# Reader_3_0.net
KiCad netlist of a schematic drawn in EAGLE
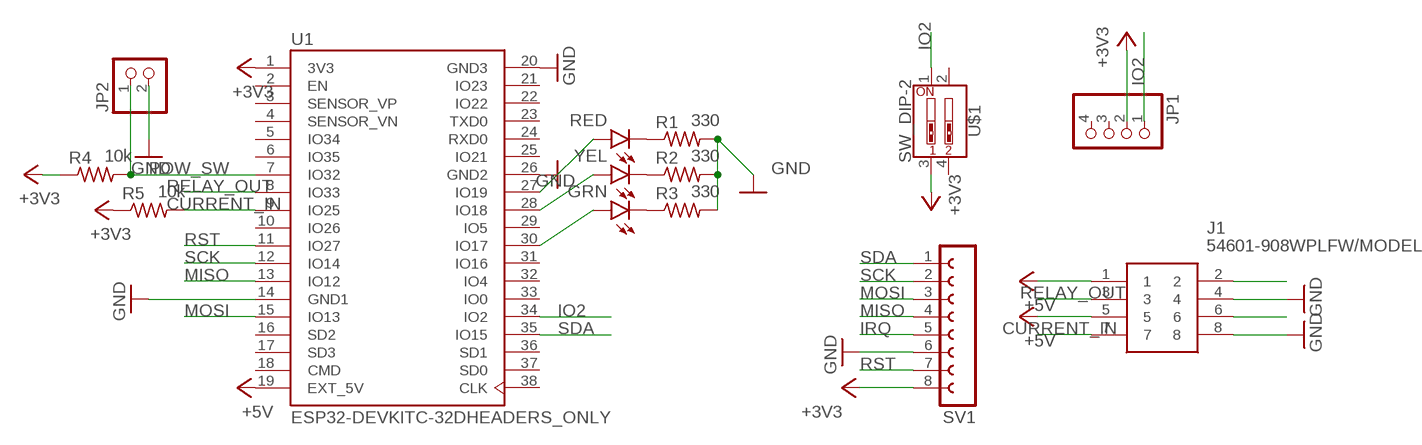
[diagram p0: schematic, sheet 1]

(export (version "E")
  (design (tool "Eeschema 10.0.6"))
  (components
    (comp (ref "GRN")
      (value "LED5MM")
      (footprint "eagle-import:LED5MM")
      (libsource (lib "eagle-import") (part "LED5MM"))
    )
    (comp (ref "J1")
      (value "54601-908WPLFW/MODEL")
      (footprint "eagle-import:HDRV4W64P254_1X4_1016X508X838B")
      (libsource (lib "eagle-import") (part "54601-908WPLFW/MODEL"))
    )
    (comp (ref "JP1")
      (value "PINHD-1X4/90")
      (footprint "eagle-import:1X04_90")
      (libsource (lib "eagle-import") (part "PINHD-1X4/90"))
    )
    (comp (ref "JP2")
      (value "PINHD-1X2/90")
      (footprint "eagle-import:1X02_90")
      (libsource (lib "eagle-import") (part "PINHD-1X2/90"))
    )
    (comp (ref "R1")
      (value "330")
      (footprint "eagle-import:0204_7")
      (libsource (lib "eagle-import") (part "R-US"))
    )
    (comp (ref "R2")
      (value "330")
      (footprint "eagle-import:0204_7")
      (libsource (lib "eagle-import") (part "R-US"))
    )
    (comp (ref "R3")
      (value "330")
      (footprint "eagle-import:0204_7")
      (libsource (lib "eagle-import") (part "R-US"))
    )
    (comp (ref "R4")
      (value "10k")
      (footprint "eagle-import:0204_7")
      (libsource (lib "eagle-import") (part "R-US"))
    )
    (comp (ref "R5")
      (value "10k")
      (footprint "eagle-import:0204_7")
      (libsource (lib "eagle-import") (part "R-US"))
    )
    (comp (ref "RED")
      (value "LED5MM")
      (footprint "eagle-import:LED5MM")
      (libsource (lib "eagle-import") (part "LED5MM"))
    )
    (comp (ref "SV1")
      (value "FE08-1")
      (footprint "eagle-import:HDR_F_1X8")
      (libsource (lib "eagle-import") (part "FE08-1"))
    )
    (comp (ref "U$1")
      (value "SW_DIP-2")
      (footprint "eagle-import:SW_DIP-2")
      (libsource (lib "eagle-import") (part "SW_DIP-2"))
    )
    (comp (ref "U1")
      (value "ESP32-DEVKITC-32DHEADERS_ONLY")
      (footprint "eagle-import:ESP32_DEVKITC_DIP")
      (fields (field (name "SPICEPREFIX") "X"))
      (libsource (lib "eagle-import") (part "ESP32-DEVKITC-32DHEADERS_ONLY"))
    )
    (comp (ref "YEL")
      (value "LED5MM")
      (footprint "eagle-import:LED5MM")
      (libsource (lib "eagle-import") (part "LED5MM"))
    )
  )
  (nets
    (net (code "1") (name "+3V3") (class "Default")
      (node (ref "JP1") (pin "2") (pinfunction "2_2") (pintype "passive"))
      (node (ref "R4") (pin "1") (pinfunction "1_1") (pintype "passive"))
      (node (ref "R5") (pin "1") (pinfunction "1_1") (pintype "passive"))
      (node (ref "SV1") (pin "8") (pinfunction "8_8") (pintype "passive"))
      (node (ref "U$1") (pin "3") (pinfunction "3_3") (pintype "passive"))
      (node (ref "U1") (pin "1") (pinfunction "3V3_1") (pintype "power_in"))
    )
    (net (code "2") (name "+5V") (class "Default")
      (node (ref "J1") (pin "1") (pinfunction "1_1") (pintype "bidirectional"))
      (node (ref "J1") (pin "5") (pinfunction "5_5") (pintype "bidirectional"))
      (node (ref "U1") (pin "19") (pinfunction "EXT_5V_19") (pintype "power_in"))
    )
    (net (code "3") (name "/CURRENT_IN") (class "Default")
      (node (ref "J1") (pin "7") (pinfunction "7_7") (pintype "bidirectional"))
      (node (ref "R5") (pin "2") (pinfunction "2_2") (pintype "passive"))
      (node (ref "U1") (pin "9") (pinfunction "IO25_9") (pintype "bidirectional"))
    )
    (net (code "4") (name "/IO2") (class "Default")
      (node (ref "JP1") (pin "1") (pinfunction "1_1") (pintype "passive"))
      (node (ref "U$1") (pin "1") (pinfunction "1_1") (pintype "passive"))
      (node (ref "U1") (pin "34") (pinfunction "IO2_34") (pintype "bidirectional"))
    )
    (net (code "5") (name "/IRQ") (class "Default")
      (node (ref "SV1") (pin "5") (pinfunction "5_5") (pintype "passive"))
    )
    (net (code "6") (name "/MISO") (class "Default")
      (node (ref "SV1") (pin "4") (pinfunction "4_4") (pintype "passive"))
      (node (ref "U1") (pin "13") (pinfunction "IO12_13") (pintype "bidirectional"))
    )
    (net (code "7") (name "/MOSI") (class "Default")
      (node (ref "SV1") (pin "3") (pinfunction "3_3") (pintype "passive"))
      (node (ref "U1") (pin "15") (pinfunction "IO13_15") (pintype "bidirectional"))
    )
    (net (code "8") (name "/POW_SW") (class "Default")
      (node (ref "JP2") (pin "1") (pinfunction "1_1") (pintype "passive"))
      (node (ref "R4") (pin "2") (pinfunction "2_2") (pintype "passive"))
      (node (ref "U1") (pin "7") (pinfunction "IO32_7") (pintype "bidirectional"))
    )
    (net (code "9") (name "/RELAY_OUT") (class "Default")
      (node (ref "J1") (pin "3") (pinfunction "3_3") (pintype "bidirectional"))
      (node (ref "U1") (pin "8") (pinfunction "IO33_8") (pintype "bidirectional"))
    )
    (net (code "10") (name "/RST") (class "Default")
      (node (ref "SV1") (pin "7") (pinfunction "7_7") (pintype "passive"))
      (node (ref "U1") (pin "11") (pinfunction "IO27_11") (pintype "bidirectional"))
    )
    (net (code "11") (name "/SCK") (class "Default")
      (node (ref "SV1") (pin "2") (pinfunction "2_2") (pintype "passive"))
      (node (ref "U1") (pin "12") (pinfunction "IO14_12") (pintype "bidirectional"))
    )
    (net (code "12") (name "/SDA") (class "Default")
      (node (ref "SV1") (pin "1") (pinfunction "1_1") (pintype "passive"))
      (node (ref "U1") (pin "35") (pinfunction "IO15_35") (pintype "bidirectional"))
    )
    (net (code "13") (name "GND") (class "Default")
      (node (ref "J1") (pin "4") (pinfunction "4_4") (pintype "bidirectional"))
      (node (ref "J1") (pin "8") (pinfunction "8_8") (pintype "bidirectional"))
      (node (ref "JP2") (pin "2") (pinfunction "2_2") (pintype "passive"))
      (node (ref "R1") (pin "2") (pinfunction "2_2") (pintype "passive"))
      (node (ref "R2") (pin "2") (pinfunction "2_2") (pintype "passive"))
      (node (ref "R3") (pin "2") (pinfunction "2_2") (pintype "passive"))
      (node (ref "SV1") (pin "6") (pinfunction "6_6") (pintype "passive"))
      (node (ref "U1") (pin "14") (pinfunction "GND1_14") (pintype "power_in"))
      (node (ref "U1") (pin "20") (pinfunction "GND3_20") (pintype "power_in"))
      (node (ref "U1") (pin "26") (pinfunction "GND2_26") (pintype "power_in"))
    )
    (net (code "14") (name "Net-(GRN-C)") (class "Default")
      (node (ref "GRN") (pin "K") (pinfunction "C_K") (pintype "passive"))
      (node (ref "R3") (pin "1") (pinfunction "1_1") (pintype "passive"))
    )
    (net (code "15") (name "Net-(RED-C)") (class "Default")
      (node (ref "R1") (pin "1") (pinfunction "1_1") (pintype "passive"))
      (node (ref "RED") (pin "K") (pinfunction "C_K") (pintype "passive"))
    )
    (net (code "16") (name "Net-(U1-IO17)") (class "Default")
      (node (ref "GRN") (pin "A") (pinfunction "A_A") (pintype "passive"))
      (node (ref "U1") (pin "30") (pinfunction "IO17_30") (pintype "bidirectional"))
    )
    (net (code "17") (name "Net-(U1-IO18)") (class "Default")
      (node (ref "U1") (pin "28") (pinfunction "IO18_28") (pintype "bidirectional"))
      (node (ref "YEL") (pin "A") (pinfunction "A_A") (pintype "passive"))
    )
    (net (code "18") (name "Net-(U1-IO19)") (class "Default")
      (node (ref "RED") (pin "A") (pinfunction "A_A") (pintype "passive"))
      (node (ref "U1") (pin "27") (pinfunction "IO19_27") (pintype "bidirectional"))
    )
    (net (code "19") (name "Net-(YEL-C)") (class "Default")
      (node (ref "R2") (pin "1") (pinfunction "1_1") (pintype "passive"))
      (node (ref "YEL") (pin "K") (pinfunction "C_K") (pintype "passive"))
    )
    (net (code "20") (name "unconnected-(J1-Pad2)") (class "Default")
      (node (ref "J1") (pin "2") (pinfunction "2_2") (pintype "bidirectional"))
    )
    (net (code "21") (name "unconnected-(J1-Pad6)") (class "Default")
      (node (ref "J1") (pin "6") (pinfunction "6_6") (pintype "bidirectional"))
    )
    (net (code "22") (name "unconnected-(JP1-Pad3)") (class "Default")
      (node (ref "JP1") (pin "3") (pinfunction "3_3") (pintype "passive"))
    )
    (net (code "23") (name "unconnected-(JP1-Pad4)") (class "Default")
      (node (ref "JP1") (pin "4") (pinfunction "4_4") (pintype "passive"))
    )
    (net (code "24") (name "unconnected-(U$1-Pad2)") (class "Default")
      (node (ref "U$1") (pin "2") (pinfunction "2_2") (pintype "passive"))
    )
    (net (code "25") (name "unconnected-(U$1-Pad4)") (class "Default")
      (node (ref "U$1") (pin "4") (pinfunction "4_4") (pintype "passive"))
    )
    (net (code "26") (name "unconnected-(U1-CLK-Pad38)") (class "Default")
      (node (ref "U1") (pin "38") (pinfunction "CLK_38") (pintype "input"))
    )
    (net (code "27") (name "unconnected-(U1-CMD-Pad18)") (class "Default")
      (node (ref "U1") (pin "18") (pinfunction "CMD_18") (pintype "bidirectional"))
    )
    (net (code "28") (name "unconnected-(U1-EN-Pad2)") (class "Default")
      (node (ref "U1") (pin "2") (pinfunction "EN_2") (pintype "input"))
    )
    (net (code "29") (name "unconnected-(U1-IO0-Pad33)") (class "Default")
      (node (ref "U1") (pin "33") (pinfunction "IO0_33") (pintype "bidirectional"))
    )
    (net (code "30") (name "unconnected-(U1-IO4-Pad32)") (class "Default")
      (node (ref "U1") (pin "32") (pinfunction "IO4_32") (pintype "bidirectional"))
    )
    (net (code "31") (name "unconnected-(U1-IO5-Pad29)") (class "Default")
      (node (ref "U1") (pin "29") (pinfunction "IO5_29") (pintype "bidirectional"))
    )
    (net (code "32") (name "unconnected-(U1-IO16-Pad31)") (class "Default")
      (node (ref "U1") (pin "31") (pinfunction "IO16_31") (pintype "bidirectional"))
    )
    (net (code "33") (name "unconnected-(U1-IO21-Pad25)") (class "Default")
      (node (ref "U1") (pin "25") (pinfunction "IO21_25") (pintype "bidirectional"))
    )
    (net (code "34") (name "unconnected-(U1-IO22-Pad22)") (class "Default")
      (node (ref "U1") (pin "22") (pinfunction "IO22_22") (pintype "bidirectional"))
    )
    (net (code "35") (name "unconnected-(U1-IO23-Pad21)") (class "Default")
      (node (ref "U1") (pin "21") (pinfunction "IO23_21") (pintype "bidirectional"))
    )
    (net (code "36") (name "unconnected-(U1-IO26-Pad10)") (class "Default")
      (node (ref "U1") (pin "10") (pinfunction "IO26_10") (pintype "bidirectional"))
    )
    (net (code "37") (name "unconnected-(U1-IO34-Pad5)") (class "Default")
      (node (ref "U1") (pin "5") (pinfunction "IO34_5") (pintype "bidirectional"))
    )
    (net (code "38") (name "unconnected-(U1-IO35-Pad6)") (class "Default")
      (node (ref "U1") (pin "6") (pinfunction "IO35_6") (pintype "bidirectional"))
    )
    (net (code "39") (name "unconnected-(U1-RXD0-Pad24)") (class "Default")
      (node (ref "U1") (pin "24") (pinfunction "RXD0_24") (pintype "input"))
    )
    (net (code "40") (name "unconnected-(U1-SD0-Pad37)") (class "Default")
      (node (ref "U1") (pin "37") (pinfunction "SD0_37") (pintype "bidirectional"))
    )
    (net (code "41") (name "unconnected-(U1-SD1-Pad36)") (class "Default")
      (node (ref "U1") (pin "36") (pinfunction "SD1_36") (pintype "bidirectional"))
    )
    (net (code "42") (name "unconnected-(U1-SD2-Pad16)") (class "Default")
      (node (ref "U1") (pin "16") (pinfunction "SD2_16") (pintype "bidirectional"))
    )
    (net (code "43") (name "unconnected-(U1-SD3-Pad17)") (class "Default")
      (node (ref "U1") (pin "17") (pinfunction "SD3_17") (pintype "bidirectional"))
    )
    (net (code "44") (name "unconnected-(U1-SENSOR_VN-Pad4)") (class "Default")
      (node (ref "U1") (pin "4") (pinfunction "SENSOR_VN_4") (pintype "input"))
    )
    (net (code "45") (name "unconnected-(U1-SENSOR_VP-Pad3)") (class "Default")
      (node (ref "U1") (pin "3") (pinfunction "SENSOR_VP_3") (pintype "input"))
    )
    (net (code "46") (name "unconnected-(U1-TXD0-Pad23)") (class "Default")
      (node (ref "U1") (pin "23") (pinfunction "TXD0_23") (pintype "output"))
    )
  )
)
